# controller.net
KiCad netlist of a schematic drawn in Altium Designer
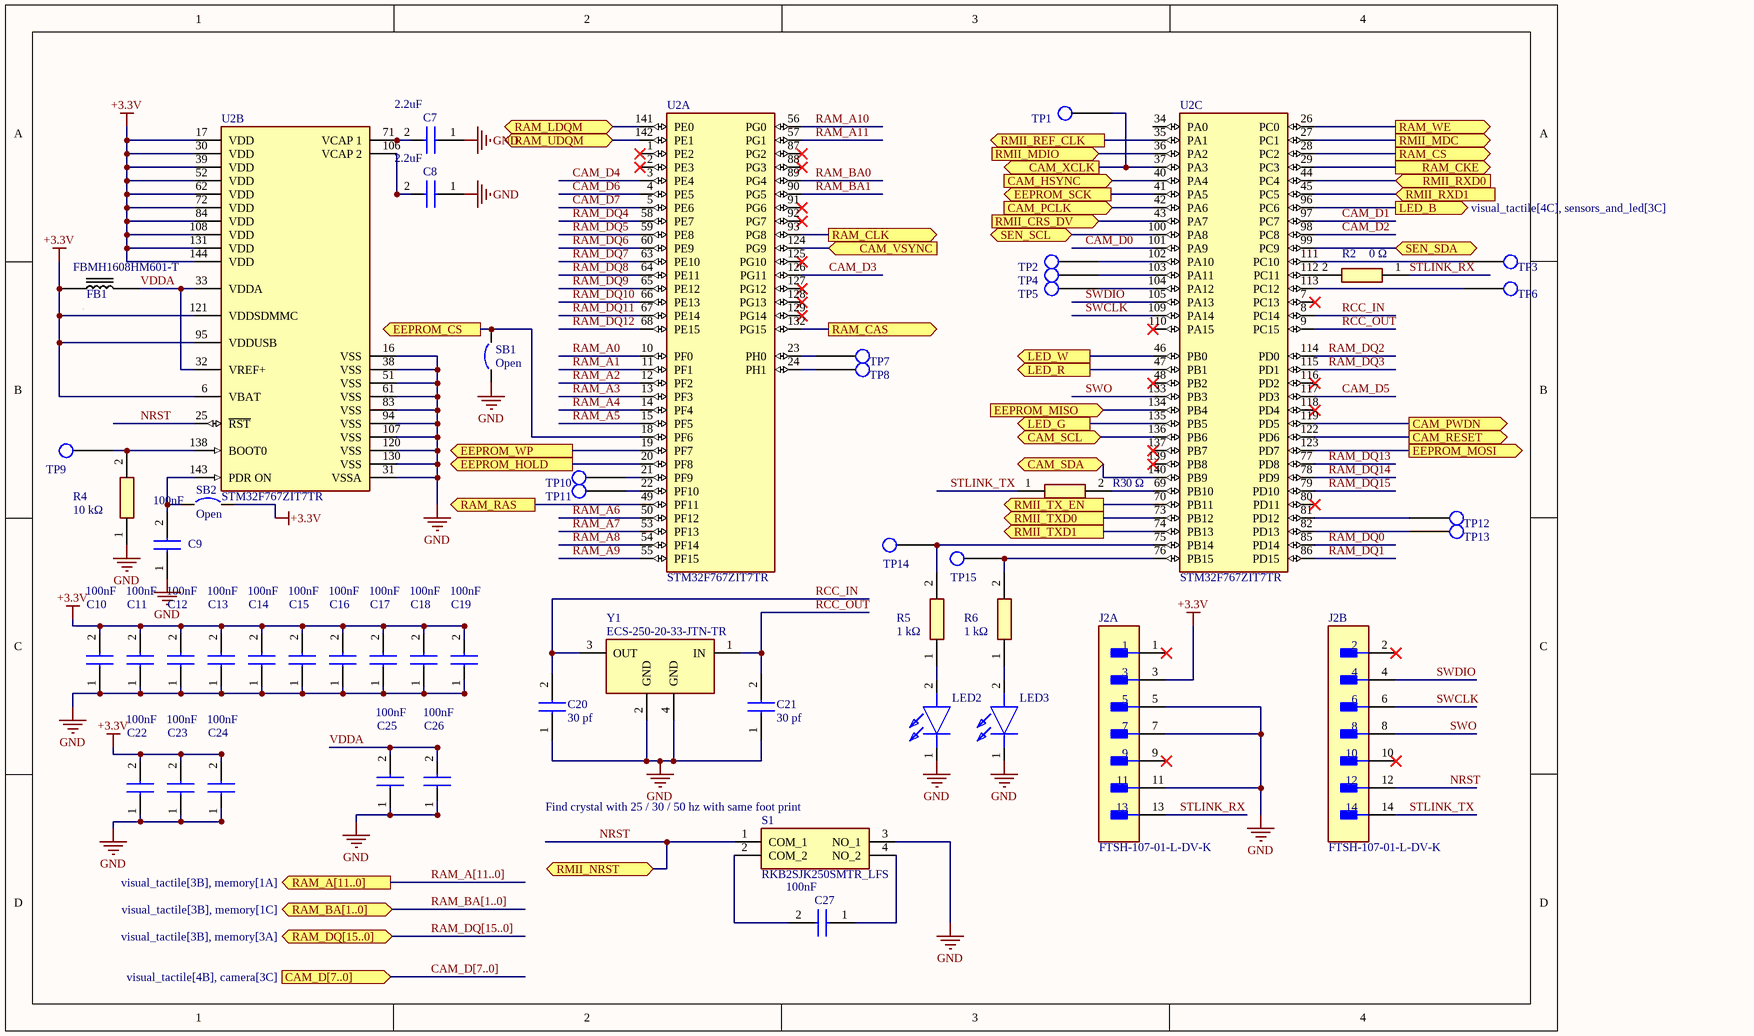
[diagram p0: controller.SchDoc]

(export (version "E")
  (design (tool "Eeschema 10.0.6"))
  (components
    (comp (ref "C7")
      (value "2.2uF")
      (footprint "PCB_library:CAPC1608X87N")
      (fields
        (field (name "MANUFACTURER_PART_NUMBER") "C0603C300J5GACTU")
        (field (name "MOUSER PART NUMBER") "80-C0603C300J5G")
        (field (name "MANUFACTURER") "Kyocera AVX")
      )
      (libsource (lib "PCB_library") (part "C0603C300J5GACTU"))
    )
    (comp (ref "C8")
      (value "2.2uF")
      (footprint "PCB_library:CAPC1608X87N")
      (fields
        (field (name "MANUFACTURER_PART_NUMBER") "C0603C300J5GACTU")
        (field (name "MOUSER PART NUMBER") "80-C0603C300J5G")
        (field (name "MANUFACTURER") "Kyocera AVX")
      )
      (libsource (lib "PCB_library") (part "C0603C300J5GACTU"))
    )
    (comp (ref "C9")
      (value "100nF")
      (footprint "PCB_library:CAPC1608X87N")
      (fields
        (field (name "MANUFACTURER_PART_NUMBER") "C0603C300J5GACTU")
        (field (name "MOUSER PART NUMBER") "80-C0603C300J5G")
        (field (name "MANUFACTURER") "TDK")
      )
      (libsource (lib "PCB_library") (part "C0603C300J5GACTU"))
    )
    (comp (ref "C10")
      (value "100nF")
      (footprint "PCB_library:CAPC1608X87N")
      (fields
        (field (name "MANUFACTURER_PART_NUMBER") "C0603C300J5GACTU")
        (field (name "MOUSER PART NUMBER") "80-C0603C300J5G")
        (field (name "MANUFACTURER") "TDK")
      )
      (libsource (lib "PCB_library") (part "C0603C300J5GACTU"))
    )
    (comp (ref "C11")
      (value "100nF")
      (footprint "PCB_library:CAPC1608X87N")
      (fields
        (field (name "MANUFACTURER_PART_NUMBER") "C0603C300J5GACTU")
        (field (name "MOUSER PART NUMBER") "80-C0603C300J5G")
        (field (name "MANUFACTURER") "TDK")
      )
      (libsource (lib "PCB_library") (part "C0603C300J5GACTU"))
    )
    (comp (ref "C12")
      (value "100nF")
      (footprint "PCB_library:CAPC1608X87N")
      (fields
        (field (name "MANUFACTURER_PART_NUMBER") "C0603C300J5GACTU")
        (field (name "MOUSER PART NUMBER") "80-C0603C300J5G")
        (field (name "MANUFACTURER") "TDK")
      )
      (libsource (lib "PCB_library") (part "C0603C300J5GACTU"))
    )
    (comp (ref "C13")
      (value "100nF")
      (footprint "PCB_library:CAPC1608X87N")
      (fields
        (field (name "MANUFACTURER_PART_NUMBER") "C0603C300J5GACTU")
        (field (name "MOUSER PART NUMBER") "80-C0603C300J5G")
        (field (name "MANUFACTURER") "TDK")
      )
      (libsource (lib "PCB_library") (part "C0603C300J5GACTU"))
    )
    (comp (ref "C14")
      (value "100nF")
      (footprint "PCB_library:CAPC1608X87N")
      (fields
        (field (name "MANUFACTURER_PART_NUMBER") "C0603C300J5GACTU")
        (field (name "MOUSER PART NUMBER") "80-C0603C300J5G")
        (field (name "MANUFACTURER") "TDK")
      )
      (libsource (lib "PCB_library") (part "C0603C300J5GACTU"))
    )
    (comp (ref "C15")
      (value "100nF")
      (footprint "PCB_library:CAPC1608X87N")
      (fields
        (field (name "MANUFACTURER_PART_NUMBER") "C0603C300J5GACTU")
        (field (name "MOUSER PART NUMBER") "80-C0603C300J5G")
        (field (name "MANUFACTURER") "TDK")
      )
      (libsource (lib "PCB_library") (part "C0603C300J5GACTU"))
    )
    (comp (ref "C16")
      (value "100nF")
      (footprint "PCB_library:CAPC1608X87N")
      (fields
        (field (name "MANUFACTURER_PART_NUMBER") "C0603C300J5GACTU")
        (field (name "MOUSER PART NUMBER") "80-C0603C300J5G")
        (field (name "MANUFACTURER") "TDK")
      )
      (libsource (lib "PCB_library") (part "C0603C300J5GACTU"))
    )
    (comp (ref "C17")
      (value "100nF")
      (footprint "PCB_library:CAPC1608X87N")
      (fields
        (field (name "MANUFACTURER_PART_NUMBER") "C0603C300J5GACTU")
        (field (name "MOUSER PART NUMBER") "80-C0603C300J5G")
        (field (name "MANUFACTURER") "TDK")
      )
      (libsource (lib "PCB_library") (part "C0603C300J5GACTU"))
    )
    (comp (ref "C18")
      (value "100nF")
      (footprint "PCB_library:CAPC1608X87N")
      (fields
        (field (name "MANUFACTURER_PART_NUMBER") "C0603C300J5GACTU")
        (field (name "MOUSER PART NUMBER") "80-C0603C300J5G")
        (field (name "MANUFACTURER") "TDK")
      )
      (libsource (lib "PCB_library") (part "C0603C300J5GACTU"))
    )
    (comp (ref "C19")
      (value "100nF")
      (footprint "PCB_library:CAPC1608X87N")
      (fields
        (field (name "MANUFACTURER_PART_NUMBER") "C0603C300J5GACTU")
        (field (name "MOUSER PART NUMBER") "80-C0603C300J5G")
        (field (name "MANUFACTURER") "TDK")
      )
      (libsource (lib "PCB_library") (part "C0603C300J5GACTU"))
    )
    (comp (ref "C20")
      (value "30 pf")
      (footprint "PCB_library:CAPC1608X87N")
      (fields
        (field (name "MANUFACTURER_PART_NUMBER") "C0603C300J5GACTU")
        (field (name "MOUSER PART NUMBER") "80-C0603C300J5G")
        (field (name "MANUFACTURER") "KEMET")
      )
      (libsource (lib "*") (part "C0603C300J5GACTU"))
    )
    (comp (ref "C21")
      (value "30 pf")
      (footprint "PCB_library:CAPC1608X87N")
      (fields
        (field (name "MANUFACTURER_PART_NUMBER") "C0603C300J5GACTU")
        (field (name "MOUSER PART NUMBER") "80-C0603C300J5G")
        (field (name "MANUFACTURER") "KEMET")
      )
      (libsource (lib "*") (part "C0603C300J5GACTU"))
    )
    (comp (ref "C22")
      (value "100nF")
      (footprint "PCB_library:CAPC1608X87N")
      (fields
        (field (name "MANUFACTURER_PART_NUMBER") "C0603C300J5GACTU")
        (field (name "MOUSER PART NUMBER") "80-C0603C300J5G")
        (field (name "MANUFACTURER") "TDK")
      )
      (libsource (lib "PCB_library") (part "C0603C300J5GACTU"))
    )
    (comp (ref "C23")
      (value "100nF")
      (footprint "PCB_library:CAPC1608X87N")
      (fields
        (field (name "MANUFACTURER_PART_NUMBER") "C0603C300J5GACTU")
        (field (name "MOUSER PART NUMBER") "80-C0603C300J5G")
        (field (name "MANUFACTURER") "TDK")
      )
      (libsource (lib "PCB_library") (part "C0603C300J5GACTU"))
    )
    (comp (ref "C24")
      (value "100nF")
      (footprint "PCB_library:CAPC1608X87N")
      (fields
        (field (name "MANUFACTURER_PART_NUMBER") "C0603C300J5GACTU")
        (field (name "MOUSER PART NUMBER") "80-C0603C300J5G")
        (field (name "MANUFACTURER") "TDK")
      )
      (libsource (lib "PCB_library") (part "C0603C300J5GACTU"))
    )
    (comp (ref "C25")
      (value "100nF")
      (footprint "PCB_library:CAPC1608X87N")
      (fields
        (field (name "MANUFACTURER_PART_NUMBER") "C0603C300J5GACTU")
        (field (name "MOUSER PART NUMBER") "80-C0603C300J5G")
        (field (name "MANUFACTURER") "TDK")
      )
      (libsource (lib "PCB_library") (part "C0603C300J5GACTU"))
    )
    (comp (ref "C26")
      (value "100nF")
      (footprint "PCB_library:CAPC1608X87N")
      (fields
        (field (name "MANUFACTURER_PART_NUMBER") "C0603C300J5GACTU")
        (field (name "MOUSER PART NUMBER") "80-C0603C300J5G")
        (field (name "MANUFACTURER") "TDK")
      )
      (libsource (lib "PCB_library") (part "C0603C300J5GACTU"))
    )
    (comp (ref "C27")
      (value "100nF")
      (footprint "PCB_library:CAPC1608X87N")
      (fields
        (field (name "MANUFACTURER_PART_NUMBER") "C0603C300J5GACTU")
        (field (name "MOUSER PART NUMBER") "80-C0603C300J5G")
        (field (name "MANUFACTURER") "TDK")
      )
      (libsource (lib "PCB_library") (part "C0603C300J5GACTU"))
    )
    (comp (ref "FB1")
      (value "FBMH1608HM601-T")
      (footprint "PCB_library:BEADC1608X90N")
      (description "Ferrite Bead")
      (fields (field (name "MOUSER PART NUMBER") "963-FBMH1608HM601-T"))
      (libsource (lib "PCB_library") (part "FBMH1608HM601-T"))
    )
    (comp (ref "J2")
      (value "FTSH-107-01-L-DV-K")
      (footprint "FP-FTSH-107-01-L-DV-K-MFG")
      (description "CONN HEADER SMD 14POS 1.27MM")
      (libsource (lib "Altium Content Vault") (part "7644e1a88aa4da17242a9b8d8257442"))
    )
    (comp (ref "LED2")
      (value "150060RS75000")
      (footprint "PCB_library:LEDC1608X80N")
      (description "LED")
      (fields (field (name "MOUSER PART NUMBER") "710-150060RS75000"))
      (libsource (lib "*") (part "150060RS75000"))
    )
    (comp (ref "LED3")
      (value "150060RS75000")
      (footprint "PCB_library:LEDC1608X80N")
      (description "LED")
      (fields (field (name "MOUSER PART NUMBER") "710-150060RS75000"))
      (libsource (lib "*") (part "150060RS75000"))
    )
    (comp (ref "R2")
      (value "0 Ω")
      (footprint "RESC1005X35N")
      (description "Resistor")
      (fields
        (field (name "MANUFACTURER_PART_NUMBER") "CPF0402B100KE")
        (field (name "MOUSER PART NUMBER") "279-CPF0402B100KE")
      )
      (libsource (lib "") (part "CPF0402B100KE_2"))
    )
    (comp (ref "R3")
      (value "0 Ω")
      (footprint "RESC1005X35N")
      (description "Resistor")
      (fields
        (field (name "MANUFACTURER_PART_NUMBER") "CPF0402B100KE")
        (field (name "MOUSER PART NUMBER") "279-CPF0402B100KE")
      )
      (libsource (lib "") (part "CPF0402B100KE_1"))
    )
    (comp (ref "R4")
      (value "10 kΩ")
      (footprint "RESC1005X35N")
      (description "Resistor")
      (fields
        (field (name "MANUFACTURER_PART_NUMBER") "CPF0402B100KE")
        (field (name "MOUSER PART NUMBER") "279-CPF0402B100KE")
      )
      (libsource (lib "*") (part "CPF0402B100KE"))
    )
    (comp (ref "R5")
      (value "1 kΩ")
      (footprint "RESC1005X35N")
      (description "Resistor")
      (fields
        (field (name "MANUFACTURER_PART_NUMBER") "CPF0402B100KE")
        (field (name "MOUSER PART NUMBER") "279-CPF0402B100KE")
      )
      (libsource (lib "*") (part "CPF0402B100KE"))
    )
    (comp (ref "R6")
      (value "1 kΩ")
      (footprint "RESC1005X35N")
      (description "Resistor")
      (fields
        (field (name "MANUFACTURER_PART_NUMBER") "CPF0402B100KE")
        (field (name "MOUSER PART NUMBER") "279-CPF0402B100KE")
      )
      (libsource (lib "*") (part "CPF0402B100KE"))
    )
    (comp (ref "S1")
      (value "RKB2SJK250SMTR_LFS")
      (footprint "PCB_library:RKB2SJK250SMTRLFS")
      (description "Switch")
      (fields
        (field (name "MANUFACTURER_PART_NUMBER") "RKB2SJK250SMTR LFS")
        (field (name "MOUSER PART NUMBER") "611-RKB2SJK250SMTRLF")
      )
      (libsource (lib "PCB_library") (part "RKB2SJK250SMTR_LFS"))
    )
    (comp (ref "SB1")
      (value "Open")
      (footprint "SB_0603")
      (description "Circuit Breaker")
      (fields (field (name "PUBLISHER") "Altium Limited"))
      (libsource (lib "PCB_library") (part "Circuit Breaker"))
    )
    (comp (ref "SB2")
      (value "Open")
      (footprint "SB_0603")
      (description "Circuit Breaker")
      (fields (field (name "PUBLISHER") "Altium Limited"))
      (libsource (lib "PCB_library") (part "Circuit Breaker"))
    )
    (comp (ref "TP1")
      (value "Test point")
      (footprint "test point")
      (libsource (lib "PCB_library") (part "Test point"))
    )
    (comp (ref "TP2")
      (value "Test point")
      (footprint "test point")
      (libsource (lib "PCB_library") (part "Test point"))
    )
    (comp (ref "TP3")
      (value "Test point")
      (footprint "test point")
      (libsource (lib "PCB_library") (part "Test point"))
    )
    (comp (ref "TP4")
      (value "Test point")
      (footprint "test point")
      (libsource (lib "PCB_library") (part "Test point"))
    )
    (comp (ref "TP5")
      (value "Test point")
      (footprint "test point")
      (libsource (lib "PCB_library") (part "Test point"))
    )
    (comp (ref "TP6")
      (value "Test point")
      (footprint "test point")
      (libsource (lib "PCB_library") (part "Test point"))
    )
    (comp (ref "TP7")
      (value "Test point")
      (footprint "test point")
      (libsource (lib "PCB_library") (part "Test point"))
    )
    (comp (ref "TP8")
      (value "Test point")
      (footprint "test point")
      (libsource (lib "PCB_library") (part "Test point"))
    )
    (comp (ref "TP9")
      (value "Test point")
      (footprint "test point")
      (libsource (lib "PCB_library") (part "Test point"))
    )
    (comp (ref "TP10")
      (value "Test point")
      (footprint "test point")
      (libsource (lib "PCB_library") (part "Test point"))
    )
    (comp (ref "TP11")
      (value "Test point")
      (footprint "test point")
      (libsource (lib "PCB_library") (part "Test point"))
    )
    (comp (ref "TP12")
      (value "Test point")
      (footprint "test point")
      (libsource (lib "PCB_library") (part "Test point"))
    )
    (comp (ref "TP13")
      (value "Test point")
      (footprint "test point")
      (libsource (lib "PCB_library") (part "Test point"))
    )
    (comp (ref "TP14")
      (value "Test point")
      (footprint "test point")
      (libsource (lib "PCB_library") (part "Test point"))
    )
    (comp (ref "TP15")
      (value "Test point")
      (footprint "test point")
      (libsource (lib "PCB_library") (part "Test point"))
    )
    (comp (ref "U2")
      (value "STM32F767ZIT7TR")
      (footprint "FP-LQFP144-1A-MFG")
      (description "ARM® Cortex®-M7 STM32F7 Microcontroller IC 32-Bit 216MHz 2MB (2M x 8) FLASH 144-LQFP (20x20)")
      (fields
        (field (name "MANUFACTURER") "STMicroelectronics")
        (field (name "OCTOPART") "https://octopart.com/stm32f767zit7tr-stmicroelectronics-104904785")
      )
      (libsource (lib "Altium Content Vault") (part "406a45637e2f7fe5f36e10d12e0b7c7"))
    )
    (comp (ref "Y1")
      (value "ECS-250-20-33-JTN-TR")
      (footprint "ECS-250-20-33-JTN-TR")
      (description "Crystal or Oscillator")
      (fields (field (name "MANUFACTURER_PART_NUMBER") "CO4605-100.000-T-TR"))
      (libsource (lib "PCB_library") (part "ECS-250-20-33-JTN-TR"))
    )
  )
  (nets
    (net (code "1") (name "+3.3V") (class "Default")
      (node (ref "C10") (pin "2") (pinfunction "2_2") (pintype "passive"))
      (node (ref "C11") (pin "2") (pinfunction "2_2") (pintype "passive"))
      (node (ref "C12") (pin "2") (pinfunction "2_2") (pintype "passive"))
      (node (ref "C13") (pin "2") (pinfunction "2_2") (pintype "passive"))
      (node (ref "C14") (pin "2") (pinfunction "2_2") (pintype "passive"))
      (node (ref "C15") (pin "2") (pinfunction "2_2") (pintype "passive"))
      (node (ref "C16") (pin "2") (pinfunction "2_2") (pintype "passive"))
      (node (ref "C17") (pin "2") (pinfunction "2_2") (pintype "passive"))
      (node (ref "C18") (pin "2") (pinfunction "2_2") (pintype "passive"))
      (node (ref "C19") (pin "2") (pinfunction "2_2") (pintype "passive"))
      (node (ref "C22") (pin "2") (pinfunction "2_2") (pintype "passive"))
      (node (ref "C23") (pin "2") (pinfunction "2_2") (pintype "passive"))
      (node (ref "C24") (pin "2") (pinfunction "2_2") (pintype "passive"))
      (node (ref "FB1") (pin "1") (pinfunction "1_1") (pintype "passive"))
      (node (ref "J2") (pin "3") (pinfunction "3_3") (pintype "passive"))
      (node (ref "SB2") (pin "2") (pinfunction "2_2") (pintype "passive"))
      (node (ref "U2") (pin "108") (pinfunction "VDD_108") (pintype "power_in"))
      (node (ref "U2") (pin "121") (pinfunction "VDDSDMMC_121") (pintype "power_in"))
      (node (ref "U2") (pin "131") (pinfunction "VDD_131") (pintype "power_in"))
      (node (ref "U2") (pin "144") (pinfunction "VDD_144") (pintype "power_in"))
      (node (ref "U2") (pin "17") (pinfunction "VDD_17") (pintype "power_in"))
      (node (ref "U2") (pin "30") (pinfunction "VDD_30") (pintype "power_in"))
      (node (ref "U2") (pin "39") (pinfunction "VDD_39") (pintype "power_in"))
      (node (ref "U2") (pin "52") (pinfunction "VDD_52") (pintype "power_in"))
      (node (ref "U2") (pin "6") (pinfunction "VBAT_6") (pintype "power_in"))
      (node (ref "U2") (pin "62") (pinfunction "VDD_62") (pintype "power_in"))
      (node (ref "U2") (pin "72") (pinfunction "VDD_72") (pintype "power_in"))
      (node (ref "U2") (pin "84") (pinfunction "VDD_84") (pintype "power_in"))
      (node (ref "U2") (pin "95") (pinfunction "VDDUSB_95") (pintype "power_in"))
    )
    (net (code "2") (name "/CAM_D0") (class "Default")
      (node (ref "U2") (pin "101") (pinfunction "PA9_101") (pintype "bidirectional"))
    )
    (net (code "3") (name "/CAM_D1") (class "Default")
      (node (ref "U2") (pin "97") (pinfunction "PC7_97") (pintype "bidirectional"))
    )
    (net (code "4") (name "/CAM_D2") (class "Default")
      (node (ref "U2") (pin "98") (pinfunction "PC8_98") (pintype "bidirectional"))
    )
    (net (code "5") (name "/CAM_D3") (class "Default")
      (node (ref "U2") (pin "126") (pinfunction "PG11_126") (pintype "bidirectional"))
    )
    (net (code "6") (name "/CAM_D4") (class "Default")
      (node (ref "U2") (pin "3") (pinfunction "PE4_3") (pintype "bidirectional"))
    )
    (net (code "7") (name "/CAM_D5") (class "Default")
      (node (ref "U2") (pin "117") (pinfunction "PD3_117") (pintype "bidirectional"))
    )
    (net (code "8") (name "/CAM_D6") (class "Default")
      (node (ref "U2") (pin "4") (pinfunction "PE5_4") (pintype "bidirectional"))
    )
    (net (code "9") (name "/CAM_D7") (class "Default")
      (node (ref "U2") (pin "5") (pinfunction "PE6_5") (pintype "bidirectional"))
    )
    (net (code "11") (name "/CAM_HSYNC") (class "Default")
      (node (ref "U2") (pin "40") (pinfunction "PA4_40") (pintype "bidirectional"))
    )
    (net (code "12") (name "/CAM_PCLK") (class "Default")
      (node (ref "U2") (pin "42") (pinfunction "PA6_42") (pintype "bidirectional"))
    )
    (net (code "13") (name "/CAM_PWDN") (class "Default")
      (node (ref "U2") (pin "119") (pinfunction "PD5_119") (pintype "bidirectional"))
    )
    (net (code "14") (name "/CAM_RESET") (class "Default")
      (node (ref "U2") (pin "122") (pinfunction "PD6_122") (pintype "bidirectional"))
    )
    (net (code "15") (name "/CAM_SCL") (class "Default")
      (node (ref "U2") (pin "136") (pinfunction "PB6_136") (pintype "bidirectional"))
    )
    (net (code "16") (name "/CAM_SDA") (class "Default")
      (node (ref "U2") (pin "140") (pinfunction "PB9_140") (pintype "bidirectional"))
    )
    (net (code "17") (name "/CAM_VSYNC") (class "Default")
      (node (ref "U2") (pin "124") (pinfunction "PG9_124") (pintype "bidirectional"))
    )
    (net (code "18") (name "/CAM_XCLK") (class "Default")
      (node (ref "TP1") (pin "1") (pinfunction "1_1") (pintype "passive"))
      (node (ref "U2") (pin "37") (pinfunction "PA3_37") (pintype "bidirectional"))
    )
    (net (code "19") (name "/EEPROM_CS") (class "Default")
      (node (ref "SB1") (pin "2") (pinfunction "2_2") (pintype "passive"))
      (node (ref "U2") (pin "18") (pinfunction "PF6_18") (pintype "bidirectional"))
    )
    (net (code "20") (name "/EEPROM_HOLD") (class "Default")
      (node (ref "U2") (pin "20") (pinfunction "PF8_20") (pintype "bidirectional"))
    )
    (net (code "21") (name "/EEPROM_MISO") (class "Default")
      (node (ref "U2") (pin "134") (pinfunction "PB4_134") (pintype "bidirectional"))
    )
    (net (code "22") (name "/EEPROM_MOSI") (class "Default")
      (node (ref "U2") (pin "123") (pinfunction "PD7_123") (pintype "bidirectional"))
    )
    (net (code "23") (name "/EEPROM_SCK") (class "Default")
      (node (ref "U2") (pin "41") (pinfunction "PA5_41") (pintype "bidirectional"))
    )
    (net (code "24") (name "/EEPROM_WP") (class "Default")
      (node (ref "U2") (pin "19") (pinfunction "PF7_19") (pintype "bidirectional"))
    )
    (net (code "25") (name "/LED_B") (class "Default")
      (node (ref "U2") (pin "96") (pinfunction "PC6_96") (pintype "bidirectional"))
    )
    (net (code "26") (name "/LED_G") (class "Default")
      (node (ref "U2") (pin "135") (pinfunction "PB5_135") (pintype "bidirectional"))
    )
    (net (code "27") (name "/LED_R") (class "Default")
      (node (ref "U2") (pin "47") (pinfunction "PB1_47") (pintype "bidirectional"))
    )
    (net (code "28") (name "/LED_W") (class "Default")
      (node (ref "U2") (pin "46") (pinfunction "PB0_46") (pintype "bidirectional"))
    )
    (net (code "29") (name "/NRST") (class "Default")
      (node (ref "J2") (pin "12") (pinfunction "12_12") (pintype "passive"))
      (node (ref "S1") (pin "1") (pinfunction "COM_1_1") (pintype "passive"))
      (node (ref "U2") (pin "25") (pinfunction "~{RST}_25") (pintype "bidirectional"))
    )
    (net (code "30") (name "/RAM_A0") (class "Default")
      (node (ref "U2") (pin "10") (pinfunction "PF0_10") (pintype "bidirectional"))
    )
    (net (code "31") (name "/RAM_A1") (class "Default")
      (node (ref "U2") (pin "11") (pinfunction "PF1_11") (pintype "bidirectional"))
    )
    (net (code "32") (name "/RAM_A2") (class "Default")
      (node (ref "U2") (pin "12") (pinfunction "PF2_12") (pintype "bidirectional"))
    )
    (net (code "33") (name "/RAM_A3") (class "Default")
      (node (ref "U2") (pin "13") (pinfunction "PF3_13") (pintype "bidirectional"))
    )
    (net (code "34") (name "/RAM_A4") (class "Default")
      (node (ref "U2") (pin "14") (pinfunction "PF4_14") (pintype "bidirectional"))
    )
    (net (code "35") (name "/RAM_A5") (class "Default")
      (node (ref "U2") (pin "15") (pinfunction "PF5_15") (pintype "bidirectional"))
    )
    (net (code "36") (name "/RAM_A6") (class "Default")
      (node (ref "U2") (pin "50") (pinfunction "PF12_50") (pintype "bidirectional"))
    )
    (net (code "37") (name "/RAM_A7") (class "Default")
      (node (ref "U2") (pin "53") (pinfunction "PF13_53") (pintype "bidirectional"))
    )
    (net (code "38") (name "/RAM_A8") (class "Default")
      (node (ref "U2") (pin "54") (pinfunction "PF14_54") (pintype "bidirectional"))
    )
    (net (code "39") (name "/RAM_A9") (class "Default")
      (node (ref "U2") (pin "55") (pinfunction "PF15_55") (pintype "bidirectional"))
    )
    (net (code "40") (name "/RAM_A10") (class "Default")
      (node (ref "U2") (pin "56") (pinfunction "PG0_56") (pintype "bidirectional"))
    )
    (net (code "41") (name "/RAM_A11") (class "Default")
      (node (ref "U2") (pin "57") (pinfunction "PG1_57") (pintype "bidirectional"))
    )
    (net (code "43") (name "/RAM_BA0") (class "Default")
      (node (ref "U2") (pin "89") (pinfunction "PG4_89") (pintype "bidirectional"))
    )
    (net (code "44") (name "/RAM_BA1") (class "Default")
      (node (ref "U2") (pin "90") (pinfunction "PG5_90") (pintype "bidirectional"))
    )
    (net (code "46") (name "/RAM_CAS") (class "Default")
      (node (ref "U2") (pin "132") (pinfunction "PG15_132") (pintype "bidirectional"))
    )
    (net (code "47") (name "/RAM_CKE") (class "Default")
      (node (ref "U2") (pin "29") (pinfunction "PC3_29") (pintype "bidirectional"))
    )
    (net (code "48") (name "/RAM_CLK") (class "Default")
      (node (ref "U2") (pin "93") (pinfunction "PG8_93") (pintype "bidirectional"))
    )
    (net (code "49") (name "/RAM_CS") (class "Default")
      (node (ref "U2") (pin "28") (pinfunction "PC2_28") (pintype "bidirectional"))
    )
    (net (code "50") (name "/RAM_DQ0") (class "Default")
      (node (ref "U2") (pin "85") (pinfunction "PD14_85") (pintype "bidirectional"))
    )
    (net (code "51") (name "/RAM_DQ1") (class "Default")
      (node (ref "U2") (pin "86") (pinfunction "PD15_86") (pintype "bidirectional"))
    )
    (net (code "52") (name "/RAM_DQ2") (class "Default")
      (node (ref "U2") (pin "114") (pinfunction "PD0_114") (pintype "bidirectional"))
    )
    (net (code "53") (name "/RAM_DQ3") (class "Default")
      (node (ref "U2") (pin "115") (pinfunction "PD1_115") (pintype "bidirectional"))
    )
    (net (code "54") (name "/RAM_DQ4") (class "Default")
      (node (ref "U2") (pin "58") (pinfunction "PE7_58") (pintype "bidirectional"))
    )
    (net (code "55") (name "/RAM_DQ5") (class "Default")
      (node (ref "U2") (pin "59") (pinfunction "PE8_59") (pintype "bidirectional"))
    )
    (net (code "56") (name "/RAM_DQ6") (class "Default")
      (node (ref "U2") (pin "60") (pinfunction "PE9_60") (pintype "bidirectional"))
    )
    (net (code "57") (name "/RAM_DQ7") (class "Default")
      (node (ref "U2") (pin "63") (pinfunction "PE10_63") (pintype "bidirectional"))
    )
    (net (code "58") (name "/RAM_DQ8") (class "Default")
      (node (ref "U2") (pin "64") (pinfunction "PE11_64") (pintype "bidirectional"))
    )
    (net (code "59") (name "/RAM_DQ9") (class "Default")
      (node (ref "U2") (pin "65") (pinfunction "PE12_65") (pintype "bidirectional"))
    )
    (net (code "60") (name "/RAM_DQ10") (class "Default")
      (node (ref "U2") (pin "66") (pinfunction "PE13_66") (pintype "bidirectional"))
    )
    (net (code "61") (name "/RAM_DQ11") (class "Default")
      (node (ref "U2") (pin "67") (pinfunction "PE14_67") (pintype "bidirectional"))
    )
    (net (code "62") (name "/RAM_DQ12") (class "Default")
      (node (ref "U2") (pin "68") (pinfunction "PE15_68") (pintype "bidirectional"))
    )
    (net (code "63") (name "/RAM_DQ13") (class "Default")
      (node (ref "U2") (pin "77") (pinfunction "PD8_77") (pintype "bidirectional"))
    )
    (net (code "64") (name "/RAM_DQ14") (class "Default")
      (node (ref "U2") (pin "78") (pinfunction "PD9_78") (pintype "bidirectional"))
    )
    (net (code "65") (name "/RAM_DQ15") (class "Default")
      (node (ref "U2") (pin "79") (pinfunction "PD10_79") (pintype "bidirectional"))
    )
    (net (code "67") (name "/RAM_LDQM") (class "Default")
      (node (ref "U2") (pin "141") (pinfunction "PE0_141") (pintype "bidirectional"))
    )
    (net (code "68") (name "/RAM_RAS") (class "Default")
      (node (ref "U2") (pin "49") (pinfunction "PF11_49") (pintype "bidirectional"))
    )
    (net (code "69") (name "/RAM_UDQM") (class "Default")
      (node (ref "U2") (pin "142") (pinfunction "PE1_142") (pintype "bidirectional"))
    )
    (net (code "70") (name "/RAM_WE") (class "Default")
      (node (ref "U2") (pin "26") (pinfunction "PC0_26") (pintype "bidirectional"))
    )
    (net (code "71") (name "/RCC_IN") (class "Default")
      (node (ref "C20") (pin "2") (pinfunction "2_2") (pintype "passive"))
      (node (ref "U2") (pin "8") (pinfunction "PC14_8") (pintype "bidirectional"))
      (node (ref "Y1") (pin "3") (pinfunction "OUT_3") (pintype "passive"))
    )
    (net (code "72") (name "/RCC_OUT") (class "Default")
      (node (ref "C21") (pin "2") (pinfunction "2_2") (pintype "passive"))
      (node (ref "U2") (pin "9") (pinfunction "PC15_9") (pintype "bidirectional"))
      (node (ref "Y1") (pin "1") (pinfunction "IN_1") (pintype "passive"))
    )
    (net (code "73") (name "/RMII_CRS_DV") (class "Default")
      (node (ref "U2") (pin "43") (pinfunction "PA7_43") (pintype "bidirectional"))
    )
    (net (code "74") (name "/RMII_MDC") (class "Default")
      (node (ref "U2") (pin "27") (pinfunction "PC1_27") (pintype "bidirectional"))
    )
    (net (code "75") (name "/RMII_MDIO") (class "Default")
      (node (ref "U2") (pin "36") (pinfunction "PA2_36") (pintype "bidirectional"))
    )
    (net (code "76") (name "/RMII_REF_CLK") (class "Default")
      (node (ref "U2") (pin "35") (pinfunction "PA1_35") (pintype "bidirectional"))
    )
    (net (code "77") (name "/RMII_RXD0") (class "Default")
      (node (ref "U2") (pin "44") (pinfunction "PC4_44") (pintype "bidirectional"))
    )
    (net (code "78") (name "/RMII_RXD1") (class "Default")
      (node (ref "U2") (pin "45") (pinfunction "PC5_45") (pintype "bidirectional"))
    )
    (net (code "79") (name "/RMII_TXD0") (class "Default")
      (node (ref "U2") (pin "73") (pinfunction "PB12_73") (pintype "bidirectional"))
    )
    (net (code "80") (name "/RMII_TXD1") (class "Default")
      (node (ref "U2") (pin "74") (pinfunction "PB13_74") (pintype "bidirectional"))
    )
    (net (code "81") (name "/RMII_TX_EN") (class "Default")
      (node (ref "U2") (pin "70") (pinfunction "PB11_70") (pintype "bidirectional"))
    )
    (net (code "82") (name "/SEN_SCL") (class "Default")
      (node (ref "U2") (pin "100") (pinfunction "PA8_100") (pintype "bidirectional"))
    )
    (net (code "83") (name "/SEN_SDA") (class "Default")
      (node (ref "U2") (pin "99") (pinfunction "PC9_99") (pintype "bidirectional"))
    )
    (net (code "84") (name "/STLINK_RX") (class "Default")
      (node (ref "J2") (pin "13") (pinfunction "13_13") (pintype "passive"))
      (node (ref "R2") (pin "1") (pinfunction "1_1") (pintype "passive"))
    )
    (net (code "85") (name "/STLINK_TX") (class "Default")
      (node (ref "J2") (pin "14") (pinfunction "14_14") (pintype "passive"))
      (node (ref "R3") (pin "1") (pinfunction "1_1") (pintype "passive"))
    )
    (net (code "86") (name "/SWCLK") (class "Default")
      (node (ref "J2") (pin "6") (pinfunction "6_6") (pintype "passive"))
      (node (ref "U2") (pin "109") (pinfunction "PA14_109") (pintype "bidirectional"))
    )
    (net (code "87") (name "/SWDIO") (class "Default")
      (node (ref "J2") (pin "4") (pinfunction "4_4") (pintype "passive"))
      (node (ref "U2") (pin "105") (pinfunction "PA13_105") (pintype "bidirectional"))
    )
    (net (code "88") (name "/SWO") (class "Default")
      (node (ref "J2") (pin "8") (pinfunction "8_8") (pintype "passive"))
      (node (ref "U2") (pin "133") (pinfunction "PB3_133") (pintype "bidirectional"))
    )
    (net (code "89") (name "/VDDA") (class "Default")
      (node (ref "C25") (pin "2") (pinfunction "2_2") (pintype "passive"))
      (node (ref "C26") (pin "2") (pinfunction "2_2") (pintype "passive"))
      (node (ref "FB1") (pin "2") (pinfunction "2_2") (pintype "passive"))
      (node (ref "U2") (pin "32") (pinfunction "VREF+_32") (pintype "power_in"))
      (node (ref "U2") (pin "33") (pinfunction "VDDA_33") (pintype "power_in"))
    )
    (net (code "90") (name "GND") (class "Default")
      (node (ref "C10") (pin "1") (pinfunction "1_1") (pintype "passive"))
      (node (ref "C11") (pin "1") (pinfunction "1_1") (pintype "passive"))
      (node (ref "C12") (pin "1") (pinfunction "1_1") (pintype "passive"))
      (node (ref "C13") (pin "1") (pinfunction "1_1") (pintype "passive"))
      (node (ref "C14") (pin "1") (pinfunction "1_1") (pintype "passive"))
      (node (ref "C15") (pin "1") (pinfunction "1_1") (pintype "passive"))
      (node (ref "C16") (pin "1") (pinfunction "1_1") (pintype "passive"))
      (node (ref "C17") (pin "1") (pinfunction "1_1") (pintype "passive"))
      (node (ref "C18") (pin "1") (pinfunction "1_1") (pintype "passive"))
      (node (ref "C19") (pin "1") (pinfunction "1_1") (pintype "passive"))
      (node (ref "C20") (pin "1") (pinfunction "1_1") (pintype "passive"))
      (node (ref "C21") (pin "1") (pinfunction "1_1") (pintype "passive"))
      (node (ref "C22") (pin "1") (pinfunction "1_1") (pintype "passive"))
      (node (ref "C23") (pin "1") (pinfunction "1_1") (pintype "passive"))
      (node (ref "C24") (pin "1") (pinfunction "1_1") (pintype "passive"))
      (node (ref "C25") (pin "1") (pinfunction "1_1") (pintype "passive"))
      (node (ref "C26") (pin "1") (pinfunction "1_1") (pintype "passive"))
      (node (ref "C7") (pin "1") (pinfunction "1_1") (pintype "passive"))
      (node (ref "C8") (pin "1") (pinfunction "1_1") (pintype "passive"))
      (node (ref "C9") (pin "1") (pinfunction "1_1") (pintype "passive"))
      (node (ref "J2") (pin "11") (pinfunction "11_11") (pintype "passive"))
      (node (ref "J2") (pin "5") (pinfunction "5_5") (pintype "passive"))
      (node (ref "J2") (pin "7") (pinfunction "7_7") (pintype "passive"))
      (node (ref "LED2") (pin "1") (pinfunction "K_1") (pintype "passive"))
      (node (ref "LED3") (pin "1") (pinfunction "K_1") (pintype "passive"))
      (node (ref "R4") (pin "1") (pinfunction "1_1") (pintype "passive"))
      (node (ref "S1") (pin "3") (pinfunction "NO_1_3") (pintype "passive"))
      (node (ref "SB1") (pin "1") (pinfunction "1_1") (pintype "passive"))
      (node (ref "U2") (pin "107") (pinfunction "VSS_107") (pintype "power_in"))
      (node (ref "U2") (pin "120") (pinfunction "VSS_120") (pintype "power_in"))
      (node (ref "U2") (pin "130") (pinfunction "VSS_130") (pintype "power_in"))
      (node (ref "U2") (pin "16") (pinfunction "VSS_16") (pintype "power_in"))
      (node (ref "U2") (pin "31") (pinfunction "VSSA_31") (pintype "power_in"))
      (node (ref "U2") (pin "38") (pinfunction "VSS_38") (pintype "power_in"))
      (node (ref "U2") (pin "51") (pinfunction "VSS_51") (pintype "power_in"))
      (node (ref "U2") (pin "61") (pinfunction "VSS_61") (pintype "power_in"))
      (node (ref "U2") (pin "83") (pinfunction "VSS_83") (pintype "power_in"))
      (node (ref "U2") (pin "94") (pinfunction "VSS_94") (pintype "power_in"))
      (node (ref "Y1") (pin "2") (pinfunction "GND_2") (pintype "passive"))
      (node (ref "Y1") (pin "4") (pinfunction "GND_4") (pintype "passive"))
    )
    (net (code "91") (name "Net-(LED2-A)") (class "Default")
      (node (ref "LED2") (pin "2") (pinfunction "A_2") (pintype "passive"))
      (node (ref "R5") (pin "1") (pinfunction "1_1") (pintype "passive"))
    )
    (net (code "92") (name "Net-(LED3-A)") (class "Default")
      (node (ref "LED3") (pin "2") (pinfunction "A_2") (pintype "passive"))
      (node (ref "R6") (pin "1") (pinfunction "1_1") (pintype "passive"))
    )
    (net (code "93") (name "Net-(S1-COM_2)") (class "Default")
      (node (ref "C27") (pin "2") (pinfunction "2_2") (pintype "passive"))
      (node (ref "S1") (pin "2") (pinfunction "COM_2_2") (pintype "passive"))
    )
    (net (code "94") (name "Net-(S1-NO_2)") (class "Default")
      (node (ref "C27") (pin "1") (pinfunction "1_1") (pintype "passive"))
      (node (ref "S1") (pin "4") (pinfunction "NO_2_4") (pintype "passive"))
    )
    (net (code "95") (name "Net-(U2A-PF9)") (class "Default")
      (node (ref "TP10") (pin "1") (pinfunction "1_1") (pintype "passive"))
      (node (ref "U2") (pin "21") (pinfunction "PF9_21") (pintype "bidirectional"))
    )
    (net (code "96") (name "Net-(U2A-PF10)") (class "Default")
      (node (ref "TP11") (pin "1") (pinfunction "1_1") (pintype "passive"))
      (node (ref "U2") (pin "22") (pinfunction "PF10_22") (pintype "bidirectional"))
    )
    (net (code "97") (name "Net-(U2A-PH0)") (class "Default")
      (node (ref "TP7") (pin "1") (pinfunction "1_1") (pintype "passive"))
      (node (ref "U2") (pin "23") (pinfunction "PH0_23") (pintype "bidirectional"))
    )
    (net (code "98") (name "Net-(U2A-PH1)") (class "Default")
      (node (ref "TP8") (pin "1") (pinfunction "1_1") (pintype "passive"))
      (node (ref "U2") (pin "24") (pinfunction "PH1_24") (pintype "bidirectional"))
    )
    (net (code "99") (name "Net-(U2B-BOOT0)") (class "Default")
      (node (ref "R4") (pin "2") (pinfunction "2_2") (pintype "passive"))
      (node (ref "TP9") (pin "1") (pinfunction "1_1") (pintype "passive"))
      (node (ref "U2") (pin "138") (pinfunction "BOOT0_138") (pintype "input"))
    )
    (net (code "100") (name "Net-(U2B-PDR_ON)") (class "Default")
      (node (ref "C9") (pin "2") (pinfunction "2_2") (pintype "passive"))
      (node (ref "SB2") (pin "1") (pinfunction "1_1") (pintype "passive"))
      (node (ref "U2") (pin "143") (pinfunction "PDR_ON_143") (pintype "input"))
    )
    (net (code "101") (name "Net-(U2B-VCAP_1)") (class "Default")
      (node (ref "C7") (pin "2") (pinfunction "2_2") (pintype "passive"))
      (node (ref "U2") (pin "71") (pinfunction "VCAP_1_71") (pintype "power_in"))
    )
    (net (code "102") (name "Net-(U2B-VCAP_2)") (class "Default")
      (node (ref "C8") (pin "2") (pinfunction "2_2") (pintype "passive"))
      (node (ref "U2") (pin "106") (pinfunction "VCAP_2_106") (pintype "power_in"))
    )
    (net (code "103") (name "Net-(U2C-PA10)") (class "Default")
      (node (ref "TP2") (pin "1") (pinfunction "1_1") (pintype "passive"))
      (node (ref "U2") (pin "102") (pinfunction "PA10_102") (pintype "bidirectional"))
    )
    (net (code "104") (name "Net-(U2C-PA11)") (class "Default")
      (node (ref "TP4") (pin "1") (pinfunction "1_1") (pintype "passive"))
      (node (ref "U2") (pin "103") (pinfunction "PA11_103") (pintype "bidirectional"))
    )
    (net (code "105") (name "Net-(U2C-PA12)") (class "Default")
      (node (ref "TP5") (pin "1") (pinfunction "1_1") (pintype "passive"))
      (node (ref "U2") (pin "104") (pinfunction "PA12_104") (pintype "bidirectional"))
    )
    (net (code "106") (name "Net-(U2C-PB10)") (class "Default")
      (node (ref "R3") (pin "2") (pinfunction "2_2") (pintype "passive"))
      (node (ref "U2") (pin "69") (pinfunction "PB10_69") (pintype "bidirectional"))
    )
    (net (code "107") (name "Net-(U2C-PB14)") (class "Default")
      (node (ref "R5") (pin "2") (pinfunction "2_2") (pintype "passive"))
      (node (ref "TP14") (pin "1") (pinfunction "1_1") (pintype "passive"))
      (node (ref "U2") (pin "75") (pinfunction "PB14_75") (pintype "bidirectional"))
    )
    (net (code "108") (name "Net-(U2C-PB15)") (class "Default")
      (node (ref "R6") (pin "2") (pinfunction "2_2") (pintype "passive"))
      (node (ref "TP15") (pin "1") (pinfunction "1_1") (pintype "passive"))
      (node (ref "U2") (pin "76") (pinfunction "PB15_76") (pintype "bidirectional"))
    )
    (net (code "109") (name "Net-(U2C-PC10)") (class "Default")
      (node (ref "TP3") (pin "1") (pinfunction "1_1") (pintype "passive"))
      (node (ref "U2") (pin "111") (pinfunction "PC10_111") (pintype "bidirectional"))
    )
    (net (code "110") (name "Net-(U2C-PC11)") (class "Default")
      (node (ref "R2") (pin "2") (pinfunction "2_2") (pintype "passive"))
      (node (ref "U2") (pin "112") (pinfunction "PC11_112") (pintype "bidirectional"))
    )
    (net (code "111") (name "Net-(U2C-PC12)") (class "Default")
      (node (ref "TP6") (pin "1") (pinfunction "1_1") (pintype "passive"))
      (node (ref "U2") (pin "113") (pinfunction "PC12_113") (pintype "bidirectional"))
    )
    (net (code "112") (name "Net-(U2C-PD12)") (class "Default")
      (node (ref "TP12") (pin "1") (pinfunction "1_1") (pintype "passive"))
      (node (ref "U2") (pin "81") (pinfunction "PD12_81") (pintype "bidirectional"))
    )
    (net (code "113") (name "Net-(U2C-PD13)") (class "Default")
      (node (ref "TP13") (pin "1") (pinfunction "1_1") (pintype "passive"))
      (node (ref "U2") (pin "82") (pinfunction "PD13_82") (pintype "bidirectional"))
    )
    (net (code "114") (name "unconnected-(J2-Pad1)") (class "Default")
      (node (ref "J2") (pin "1") (pinfunction "1_1") (pintype "passive+no_connect"))
    )
    (net (code "115") (name "unconnected-(J2-Pad2)") (class "Default")
      (node (ref "J2") (pin "2") (pinfunction "2_2") (pintype "passive+no_connect"))
    )
    (net (code "116") (name "unconnected-(J2-Pad9)") (class "Default")
      (node (ref "J2") (pin "9") (pinfunction "9_9") (pintype "passive+no_connect"))
    )
    (net (code "117") (name "unconnected-(J2-Pad10)") (class "Default")
      (node (ref "J2") (pin "10") (pinfunction "10_10") (pintype "passive+no_connect"))
    )
    (net (code "118") (name "unconnected-(U2A-PE2-Pad1)") (class "Default")
      (node (ref "U2") (pin "1") (pinfunction "PE2_1") (pintype "bidirectional+no_connect"))
    )
    (net (code "119") (name "unconnected-(U2A-PE3-Pad2)") (class "Default")
      (node (ref "U2") (pin "2") (pinfunction "PE3_2") (pintype "bidirectional+no_connect"))
    )
    (net (code "120") (name "unconnected-(U2A-PG2-Pad87)") (class "Default")
      (node (ref "U2") (pin "87") (pinfunction "PG2_87") (pintype "bidirectional+no_connect"))
    )
    (net (code "121") (name "unconnected-(U2A-PG3-Pad88)") (class "Default")
      (node (ref "U2") (pin "88") (pinfunction "PG3_88") (pintype "bidirectional+no_connect"))
    )
    (net (code "122") (name "unconnected-(U2A-PG6-Pad91)") (class "Default")
      (node (ref "U2") (pin "91") (pinfunction "PG6_91") (pintype "bidirectional+no_connect"))
    )
    (net (code "123") (name "unconnected-(U2A-PG7-Pad92)") (class "Default")
      (node (ref "U2") (pin "92") (pinfunction "PG7_92") (pintype "bidirectional+no_connect"))
    )
    (net (code "124") (name "unconnected-(U2A-PG10-Pad125)") (class "Default")
      (node (ref "U2") (pin "125") (pinfunction "PG10_125") (pintype "bidirectional+no_connect"))
    )
    (net (code "125") (name "unconnected-(U2A-PG12-Pad127)") (class "Default")
      (node (ref "U2") (pin "127") (pinfunction "PG12_127") (pintype "bidirectional+no_connect"))
    )
    (net (code "126") (name "unconnected-(U2A-PG13-Pad128)") (class "Default")
      (node (ref "U2") (pin "128") (pinfunction "PG13_128") (pintype "bidirectional+no_connect"))
    )
    (net (code "127") (name "unconnected-(U2A-PG14-Pad129)") (class "Default")
      (node (ref "U2") (pin "129") (pinfunction "PG14_129") (pintype "bidirectional+no_connect"))
    )
    (net (code "128") (name "unconnected-(U2C-PA0-Pad34)") (class "Default")
      (node (ref "U2") (pin "34") (pinfunction "PA0_34") (pintype "bidirectional"))
    )
    (net (code "129") (name "unconnected-(U2C-PA15-Pad110)") (class "Default")
      (node (ref "U2") (pin "110") (pinfunction "PA15_110") (pintype "bidirectional+no_connect"))
    )
    (net (code "130") (name "unconnected-(U2C-PB2-Pad48)") (class "Default")
      (node (ref "U2") (pin "48") (pinfunction "PB2_48") (pintype "bidirectional+no_connect"))
    )
    (net (code "131") (name "unconnected-(U2C-PB7-Pad137)") (class "Default")
      (node (ref "U2") (pin "137") (pinfunction "PB7_137") (pintype "bidirectional+no_connect"))
    )
    (net (code "132") (name "unconnected-(U2C-PB8-Pad139)") (class "Default")
      (node (ref "U2") (pin "139") (pinfunction "PB8_139") (pintype "bidirectional+no_connect"))
    )
    (net (code "133") (name "unconnected-(U2C-PC13-Pad7)") (class "Default")
      (node (ref "U2") (pin "7") (pinfunction "PC13_7") (pintype "bidirectional+no_connect"))
    )
    (net (code "134") (name "unconnected-(U2C-PD2-Pad116)") (class "Default")
      (node (ref "U2") (pin "116") (pinfunction "PD2_116") (pintype "bidirectional+no_connect"))
    )
    (net (code "135") (name "unconnected-(U2C-PD4-Pad118)") (class "Default")
      (node (ref "U2") (pin "118") (pinfunction "PD4_118") (pintype "bidirectional+no_connect"))
    )
    (net (code "136") (name "unconnected-(U2C-PD11-Pad80)") (class "Default")
      (node (ref "U2") (pin "80") (pinfunction "PD11_80") (pintype "bidirectional+no_connect"))
    )
  )
)
